# rpisupply-relay.net
KiCad netlist of a schematic drawn in EAGLE
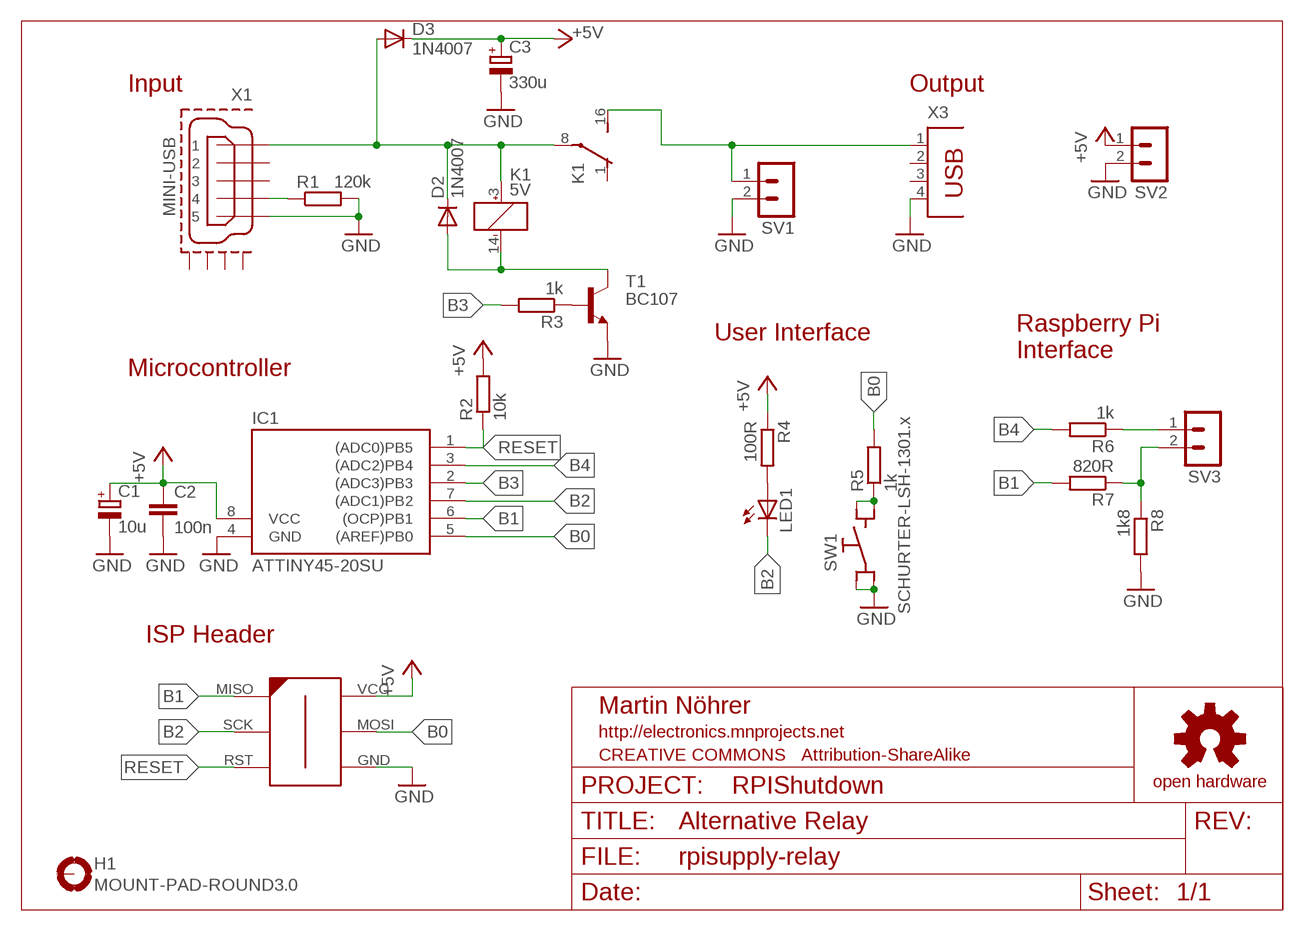
[diagram p0: schematic, sheet 1]

(export (version "E")
  (design (tool "Eeschema 10.0.6"))
  (components
    (comp (ref "C1")
      (value "10u")
      (footprint "eagle-import:SMC_C")
      (libsource (lib "eagle-import") (part "CPOL-EUSMCC"))
    )
    (comp (ref "C2")
      (value "100n")
      (footprint "eagle-import:C0805")
      (libsource (lib "eagle-import") (part "C-EUC0805"))
    )
    (comp (ref "C3")
      (value "330u")
      (footprint "eagle-import:SMC_C")
      (libsource (lib "eagle-import") (part "CPOL-EUSMCC"))
    )
    (comp (ref "D2")
      (value "1N4007")
      (footprint "eagle-import:DO41-10")
      (libsource (lib "eagle-import") (part "1N4004"))
    )
    (comp (ref "D3")
      (value "1N4007")
      (footprint "eagle-import:DO41-10")
      (libsource (lib "eagle-import") (part "1N4004"))
    )
    (comp (ref "H1")
      (value "MOUNT-PAD-ROUND3.0")
      (footprint "eagle-import:3,0-PAD")
      (libsource (lib "eagle-import") (part "MOUNT-PAD-ROUND3.0"))
    )
    (comp (ref "IC1")
      (value "ATTINY45-20SU")
      (footprint "eagle-import:SOIC8")
      (libsource (lib "eagle-import") (part "TINY25/45/85-20SU"))
    )
    (comp (ref "K1")
      (value "5V")
      (footprint "eagle-import:DR-1")
      (fields (field (name "MPN") "DR-5V"))
      (libsource (lib "eagle-import") (part "DR-V5"))
    )
    (comp (ref "LED1")
      (value "LEDSML0805")
      (footprint "eagle-import:SML0805")
      (libsource (lib "eagle-import") (part "LEDSML0805"))
    )
    (comp (ref "R1")
      (value "120k")
      (footprint "eagle-import:R0805")
      (libsource (lib "eagle-import") (part "R-EU_R0805"))
    )
    (comp (ref "R2")
      (value "10k")
      (footprint "eagle-import:R0805")
      (libsource (lib "eagle-import") (part "R-EU_R0805"))
    )
    (comp (ref "R3")
      (value "1k")
      (footprint "eagle-import:R0805")
      (libsource (lib "eagle-import") (part "R-EU_R0805"))
    )
    (comp (ref "R4")
      (value "100R")
      (footprint "eagle-import:R0805")
      (libsource (lib "eagle-import") (part "R-EU_R0805"))
    )
    (comp (ref "R5")
      (value "1k")
      (footprint "eagle-import:R0805")
      (libsource (lib "eagle-import") (part "R-EU_R0805"))
    )
    (comp (ref "R6")
      (value "1k")
      (footprint "eagle-import:R0805")
      (libsource (lib "eagle-import") (part "R-EU_R0805"))
    )
    (comp (ref "R7")
      (value "820R")
      (footprint "eagle-import:R0805")
      (libsource (lib "eagle-import") (part "R-EU_R0805"))
    )
    (comp (ref "R8")
      (value "1k8")
      (footprint "eagle-import:R0805")
      (libsource (lib "eagle-import") (part "R-EU_R0805"))
    )
    (comp (ref "SV1")
      (value "MA02-1R")
      (footprint "eagle-import:MA02-1")
      (libsource (lib "eagle-import") (part "MA02-1R"))
    )
    (comp (ref "SV2")
      (value "MA02-1R")
      (footprint "eagle-import:MA02-1")
      (libsource (lib "eagle-import") (part "MA02-1R"))
    )
    (comp (ref "SV3")
      (value "MA02-1R")
      (footprint "eagle-import:MA02-1")
      (libsource (lib "eagle-import") (part "MA02-1R"))
    )
    (comp (ref "SW1")
      (value "SCHURTER-LSH-1301.x")
      (footprint "eagle-import:LSH")
      (libsource (lib "eagle-import") (part "SCHURTER-LSH-1301.9319"))
    )
    (comp (ref "T1")
      (value "BC107")
      (footprint "eagle-import:TO18")
      (libsource (lib "eagle-import") (part "BC107"))
    )
    (comp (ref "X1")
      (value "MINI-USB")
      (footprint "eagle-import:UX60-MB-5ST")
      (libsource (lib "eagle-import") (part "MINI-USB-SHIELD-UX60-MB-5ST"))
    )
    (comp (ref "X2")
      (value "AVR-ISP-6-EDGE")
      (footprint "eagle-import:6PAD_ISP")
      (libsource (lib "eagle-import") (part "AVR-ISP-6-EDGE"))
    )
    (comp (ref "X3")
      (value "PN87520")
      (footprint "eagle-import:PN87520")
      (libsource (lib "eagle-import") (part "PN87520"))
    )
  )
  (nets
    (net (code "1") (name "+5V") (class "Default")
      (node (ref "C1") (pin "+") (pinfunction "+_+") (pintype "passive"))
      (node (ref "C2") (pin "1") (pinfunction "1_1") (pintype "passive"))
      (node (ref "C3") (pin "+") (pinfunction "+_+") (pintype "passive"))
      (node (ref "D3") (pin "C") (pinfunction "C_C") (pintype "passive"))
      (node (ref "IC1") (pin "8") (pinfunction "VCC_8") (pintype "power_in"))
      (node (ref "R2") (pin "2") (pinfunction "2_2") (pintype "passive"))
      (node (ref "R4") (pin "1") (pinfunction "1_1") (pintype "passive"))
      (node (ref "SV2") (pin "1") (pinfunction "1_1") (pintype "passive"))
      (node (ref "X2") (pin "VCC") (pinfunction "P$6_VCC") (pintype "bidirectional"))
    )
    (net (code "2") (name "B0") (class "Default")
      (node (ref "IC1") (pin "5") (pinfunction "(AREF)PB0_5") (pintype "bidirectional"))
      (node (ref "R5") (pin "2") (pinfunction "2_2") (pintype "passive"))
      (node (ref "X2") (pin "MOSI") (pinfunction "P$5_MOSI") (pintype "bidirectional"))
    )
    (net (code "3") (name "B1") (class "Default")
      (node (ref "IC1") (pin "6") (pinfunction "(OCP)PB1_6") (pintype "bidirectional"))
      (node (ref "R7") (pin "2") (pinfunction "2_2") (pintype "passive"))
      (node (ref "X2") (pin "MISO") (pinfunction "P$1_MISO") (pintype "bidirectional"))
    )
    (net (code "4") (name "B2") (class "Default")
      (node (ref "IC1") (pin "7") (pinfunction "(ADC1)PB2_7") (pintype "bidirectional"))
      (node (ref "LED1") (pin "C") (pinfunction "C_C") (pintype "passive"))
      (node (ref "X2") (pin "SCK") (pinfunction "P$2_SCK") (pintype "bidirectional"))
    )
    (net (code "5") (name "B3") (class "Default")
      (node (ref "IC1") (pin "2") (pinfunction "(ADC3)PB3_2") (pintype "bidirectional"))
      (node (ref "R3") (pin "2") (pinfunction "2_2") (pintype "passive"))
    )
    (net (code "6") (name "B4") (class "Default")
      (node (ref "IC1") (pin "3") (pinfunction "(ADC2)PB4_3") (pintype "bidirectional"))
      (node (ref "R6") (pin "2") (pinfunction "2_2") (pintype "passive"))
    )
    (net (code "7") (name "GND") (class "Default")
      (node (ref "C1") (pin "-") (pinfunction "-_-") (pintype "passive"))
      (node (ref "C2") (pin "2") (pinfunction "2_2") (pintype "passive"))
      (node (ref "C3") (pin "-") (pinfunction "-_-") (pintype "passive"))
      (node (ref "IC1") (pin "4") (pinfunction "GND_4") (pintype "power_in"))
      (node (ref "R1") (pin "2") (pinfunction "2_2") (pintype "passive"))
      (node (ref "R8") (pin "2") (pinfunction "2_2") (pintype "passive"))
      (node (ref "SV1") (pin "2") (pinfunction "2_2") (pintype "passive"))
      (node (ref "SV2") (pin "2") (pinfunction "2_2") (pintype "passive"))
      (node (ref "SW1") (pin "C1") (pinfunction "C_C1") (pintype "passive"))
      (node (ref "SW1") (pin "C2") (pinfunction "C_C2") (pintype "passive"))
      (node (ref "T1") (pin "1") (pinfunction "E_1") (pintype "passive"))
      (node (ref "X1") (pin "5") (pinfunction "5_5") (pintype "input"))
      (node (ref "X2") (pin "GND") (pinfunction "P$4_GND") (pintype "bidirectional"))
      (node (ref "X3") (pin "4") (pinfunction "4_4") (pintype "passive"))
    )
    (net (code "8") (name "Net-(K1A-+)") (class "Default")
      (node (ref "D2") (pin "C") (pinfunction "C_C") (pintype "passive"))
      (node (ref "D3") (pin "A") (pinfunction "A_A") (pintype "passive"))
      (node (ref "K1") (pin "3") (pinfunction "+_3") (pintype "passive"))
      (node (ref "K1") (pin "8") (pinfunction "P_8") (pintype "passive"))
      (node (ref "X1") (pin "1") (pinfunction "1_1") (pintype "input"))
    )
    (net (code "9") (name "Net-(K1A--)") (class "Default")
      (node (ref "D2") (pin "A") (pinfunction "A_A") (pintype "passive"))
      (node (ref "K1") (pin "14") (pinfunction "-_14") (pintype "passive"))
      (node (ref "T1") (pin "3") (pinfunction "C_3") (pintype "passive"))
    )
    (net (code "10") (name "Net-(K1B-S)") (class "Default")
      (node (ref "K1") (pin "16") (pinfunction "S_16") (pintype "passive"))
      (node (ref "SV1") (pin "1") (pinfunction "1_1") (pintype "passive"))
      (node (ref "X3") (pin "1") (pinfunction "1_1") (pintype "passive"))
    )
    (net (code "11") (name "Net-(LED1-PadA)") (class "Default")
      (node (ref "LED1") (pin "A") (pinfunction "A_A") (pintype "passive"))
      (node (ref "R4") (pin "2") (pinfunction "2_2") (pintype "passive"))
    )
    (net (code "12") (name "Net-(R1-Pad1)") (class "Default")
      (node (ref "R1") (pin "1") (pinfunction "1_1") (pintype "passive"))
      (node (ref "X1") (pin "4") (pinfunction "4_4") (pintype "input"))
    )
    (net (code "13") (name "Net-(R5-Pad1)") (class "Default")
      (node (ref "R5") (pin "1") (pinfunction "1_1") (pintype "passive"))
      (node (ref "SW1") (pin "NO1") (pinfunction "NO_NO1") (pintype "passive"))
      (node (ref "SW1") (pin "NO2") (pinfunction "NO_NO2") (pintype "passive"))
    )
    (net (code "14") (name "Net-(R6-Pad1)") (class "Default")
      (node (ref "R6") (pin "1") (pinfunction "1_1") (pintype "passive"))
      (node (ref "SV3") (pin "1") (pinfunction "1_1") (pintype "passive"))
    )
    (net (code "15") (name "Net-(R7-Pad1)") (class "Default")
      (node (ref "R7") (pin "1") (pinfunction "1_1") (pintype "passive"))
      (node (ref "R8") (pin "1") (pinfunction "1_1") (pintype "passive"))
      (node (ref "SV3") (pin "2") (pinfunction "2_2") (pintype "passive"))
    )
    (net (code "16") (name "Net-(T1-B)") (class "Default")
      (node (ref "R3") (pin "1") (pinfunction "1_1") (pintype "passive"))
      (node (ref "T1") (pin "2") (pinfunction "B_2") (pintype "passive"))
    )
    (net (code "17") (name "RESET") (class "Default")
      (node (ref "IC1") (pin "1") (pinfunction "(ADC0)PB5_1") (pintype "bidirectional"))
      (node (ref "R2") (pin "1") (pinfunction "1_1") (pintype "passive"))
      (node (ref "X2") (pin "RST") (pinfunction "P$3_RST") (pintype "bidirectional"))
    )
    (net (code "18") (name "unconnected-(H1-MOUNT-PadB3,0)") (class "Default")
      (node (ref "H1") (pin "B3,0") (pinfunction "MOUNT_B3,0") (pintype "passive"))
    )
    (net (code "19") (name "unconnected-(K1B-O-Pad1)") (class "Default")
      (node (ref "K1") (pin "1") (pinfunction "O_1") (pintype "passive"))
    )
    (net (code "20") (name "unconnected-(X1-GND1-PadM1)") (class "Default")
      (node (ref "X1") (pin "M1") (pinfunction "GND1_M1") (pintype "bidirectional"))
    )
    (net (code "21") (name "unconnected-(X1-GND2-PadM2)") (class "Default")
      (node (ref "X1") (pin "M2") (pinfunction "GND2_M2") (pintype "bidirectional"))
    )
    (net (code "22") (name "unconnected-(X1-GND3-PadM3)") (class "Default")
      (node (ref "X1") (pin "M3") (pinfunction "GND3_M3") (pintype "bidirectional"))
    )
    (net (code "23") (name "unconnected-(X1-GND4-PadM4)") (class "Default")
      (node (ref "X1") (pin "M4") (pinfunction "GND4_M4") (pintype "bidirectional"))
    )
    (net (code "24") (name "unconnected-(X1-Pad2)") (class "Default")
      (node (ref "X1") (pin "2") (pinfunction "2_2") (pintype "input"))
    )
    (net (code "25") (name "unconnected-(X1-Pad3)") (class "Default")
      (node (ref "X1") (pin "3") (pinfunction "3_3") (pintype "input"))
    )
    (net (code "26") (name "unconnected-(X3-Pad2)") (class "Default")
      (node (ref "X3") (pin "2") (pinfunction "2_2") (pintype "passive"))
    )
    (net (code "27") (name "unconnected-(X3-Pad3)") (class "Default")
      (node (ref "X3") (pin "3") (pinfunction "3_3") (pintype "passive"))
    )
  )
)
